# DS2482-LC24XX-breakout.net
KiCad netlist of a schematic drawn in EAGLE
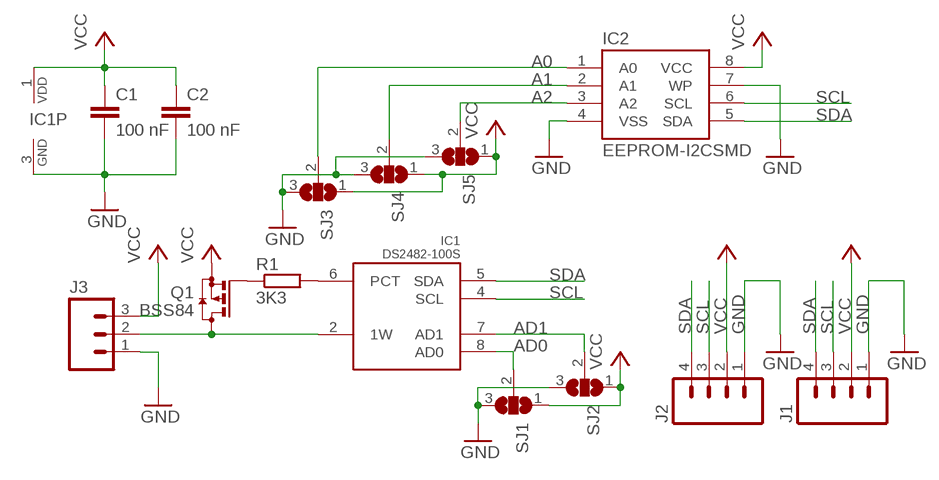
[diagram p0: schematic, sheet 1]

(export (version "E")
  (design (tool "Eeschema 10.0.6"))
  (components
    (comp (ref "C1")
      (value "100 nF")
      (footprint "eagle-import:C0603")
      (libsource (lib "eagle-import") (part "C-EUC0603"))
    )
    (comp (ref "C2")
      (value "100 nF")
      (footprint "eagle-import:C0603")
      (libsource (lib "eagle-import") (part "C-EUC0603"))
    )
    (comp (ref "IC1")
      (value "DS2482-100S")
      (footprint "eagle-import:SO08")
      (libsource (lib "eagle-import") (part "DS2482-100S"))
    )
    (comp (ref "IC2")
      (value "EEPROM-I2CSMD")
      (footprint "eagle-import:SO08")
      (libsource (lib "eagle-import") (part "EEPROM-I2CSMD"))
    )
    (comp (ref "J1")
      (value "M04PTH")
      (footprint "eagle-import:1X04")
      (libsource (lib "eagle-import") (part "M04PTH"))
    )
    (comp (ref "J2")
      (value "M04PTH")
      (footprint "eagle-import:1X04")
      (libsource (lib "eagle-import") (part "M04PTH"))
    )
    (comp (ref "J3")
      (value "M03PTH")
      (footprint "eagle-import:1X03")
      (libsource (lib "eagle-import") (part "M03PTH"))
    )
    (comp (ref "Q1")
      (value "BSS84")
      (footprint "eagle-import:SOT23")
      (libsource (lib "eagle-import") (part "BSS84"))
    )
    (comp (ref "R1")
      (value "3K3")
      (footprint "eagle-import:R0805")
      (libsource (lib "eagle-import") (part "R-EU_R0805"))
    )
    (comp (ref "SJ1")
      (value "SJ2W")
      (footprint "eagle-import:SJ_2")
      (libsource (lib "eagle-import") (part "SJ2W"))
    )
    (comp (ref "SJ2")
      (value "SJ2W")
      (footprint "eagle-import:SJ_2")
      (libsource (lib "eagle-import") (part "SJ2W"))
    )
    (comp (ref "SJ3")
      (value "SJ2W")
      (footprint "eagle-import:SJ_2")
      (libsource (lib "eagle-import") (part "SJ2W"))
    )
    (comp (ref "SJ4")
      (value "SJ2W")
      (footprint "eagle-import:SJ_2")
      (libsource (lib "eagle-import") (part "SJ2W"))
    )
    (comp (ref "SJ5")
      (value "SJ2W")
      (footprint "eagle-import:SJ_2")
      (libsource (lib "eagle-import") (part "SJ2W"))
    )
  )
  (nets
    (net (code "1") (name "/A0") (class "Default")
      (node (ref "IC2") (pin "1") (pinfunction "A0_1") (pintype "bidirectional"))
      (node (ref "SJ3") (pin "2") (pinfunction "2_2") (pintype "passive"))
    )
    (net (code "2") (name "/A1") (class "Default")
      (node (ref "IC2") (pin "2") (pinfunction "A1_2") (pintype "bidirectional"))
      (node (ref "SJ4") (pin "2") (pinfunction "2_2") (pintype "passive"))
    )
    (net (code "3") (name "/A2") (class "Default")
      (node (ref "IC2") (pin "3") (pinfunction "A2_3") (pintype "bidirectional"))
      (node (ref "SJ5") (pin "2") (pinfunction "2_2") (pintype "passive"))
    )
    (net (code "4") (name "/AD0") (class "Default")
      (node (ref "IC1") (pin "8") (pinfunction "AD0_8") (pintype "input"))
      (node (ref "SJ1") (pin "2") (pinfunction "2_2") (pintype "passive"))
    )
    (net (code "5") (name "/AD1") (class "Default")
      (node (ref "IC1") (pin "7") (pinfunction "AD1_7") (pintype "input"))
      (node (ref "SJ2") (pin "2") (pinfunction "2_2") (pintype "passive"))
    )
    (net (code "6") (name "/SCL") (class "Default")
      (node (ref "IC1") (pin "4") (pinfunction "SCL_4") (pintype "input"))
      (node (ref "IC2") (pin "6") (pinfunction "SCL_6") (pintype "bidirectional"))
      (node (ref "J1") (pin "3") (pinfunction "3_3") (pintype "passive"))
      (node (ref "J2") (pin "3") (pinfunction "3_3") (pintype "passive"))
    )
    (net (code "7") (name "/SDA") (class "Default")
      (node (ref "IC1") (pin "5") (pinfunction "SDA_5") (pintype "bidirectional"))
      (node (ref "IC2") (pin "5") (pinfunction "SDA_5") (pintype "bidirectional"))
      (node (ref "J1") (pin "4") (pinfunction "4_4") (pintype "passive"))
      (node (ref "J2") (pin "4") (pinfunction "4_4") (pintype "passive"))
    )
    (net (code "8") (name "GND") (class "Default")
      (node (ref "C1") (pin "2") (pinfunction "2_2") (pintype "passive"))
      (node (ref "C2") (pin "2") (pinfunction "2_2") (pintype "passive"))
      (node (ref "IC1") (pin "3") (pinfunction "GND_3") (pintype "power_in"))
      (node (ref "IC2") (pin "4") (pinfunction "VSS_4") (pintype "power_in"))
      (node (ref "IC2") (pin "7") (pinfunction "WP_7") (pintype "bidirectional"))
      (node (ref "J1") (pin "1") (pinfunction "1_1") (pintype "passive"))
      (node (ref "J2") (pin "1") (pinfunction "1_1") (pintype "passive"))
      (node (ref "J3") (pin "1") (pinfunction "1_1") (pintype "passive"))
      (node (ref "SJ1") (pin "3") (pinfunction "3_3") (pintype "passive"))
      (node (ref "SJ2") (pin "3") (pinfunction "3_3") (pintype "passive"))
      (node (ref "SJ3") (pin "3") (pinfunction "3_3") (pintype "passive"))
      (node (ref "SJ4") (pin "3") (pinfunction "3_3") (pintype "passive"))
      (node (ref "SJ5") (pin "3") (pinfunction "3_3") (pintype "passive"))
    )
    (net (code "9") (name "Net-(IC1A-1W)") (class "Default")
      (node (ref "IC1") (pin "2") (pinfunction "1W_2") (pintype "open_collector"))
      (node (ref "J3") (pin "2") (pinfunction "2_2") (pintype "passive"))
      (node (ref "Q1") (pin "3") (pinfunction "D_3") (pintype "passive"))
    )
    (net (code "10") (name "Net-(IC1A-PCT)") (class "Default")
      (node (ref "IC1") (pin "6") (pinfunction "PCT_6") (pintype "output"))
      (node (ref "R1") (pin "2") (pinfunction "2_2") (pintype "passive"))
    )
    (net (code "11") (name "Net-(Q1-G)") (class "Default")
      (node (ref "Q1") (pin "1") (pinfunction "G_1") (pintype "passive"))
      (node (ref "R1") (pin "1") (pinfunction "1_1") (pintype "passive"))
    )
    (net (code "12") (name "VCC") (class "Default")
      (node (ref "C1") (pin "1") (pinfunction "1_1") (pintype "passive"))
      (node (ref "C2") (pin "1") (pinfunction "1_1") (pintype "passive"))
      (node (ref "IC1") (pin "1") (pinfunction "VDD_1") (pintype "power_in"))
      (node (ref "IC2") (pin "8") (pinfunction "VCC_8") (pintype "power_in"))
      (node (ref "J1") (pin "2") (pinfunction "2_2") (pintype "passive"))
      (node (ref "J2") (pin "2") (pinfunction "2_2") (pintype "passive"))
      (node (ref "J3") (pin "3") (pinfunction "3_3") (pintype "passive"))
      (node (ref "Q1") (pin "2") (pinfunction "S_2") (pintype "passive"))
      (node (ref "SJ1") (pin "1") (pinfunction "1_1") (pintype "passive"))
      (node (ref "SJ2") (pin "1") (pinfunction "1_1") (pintype "passive"))
      (node (ref "SJ3") (pin "1") (pinfunction "1_1") (pintype "passive"))
      (node (ref "SJ4") (pin "1") (pinfunction "1_1") (pintype "passive"))
      (node (ref "SJ5") (pin "1") (pinfunction "1_1") (pintype "passive"))
    )
  )
)
